# RumiCarGen3-CM5.net
KiCad netlist of a schematic drawn in EAGLE
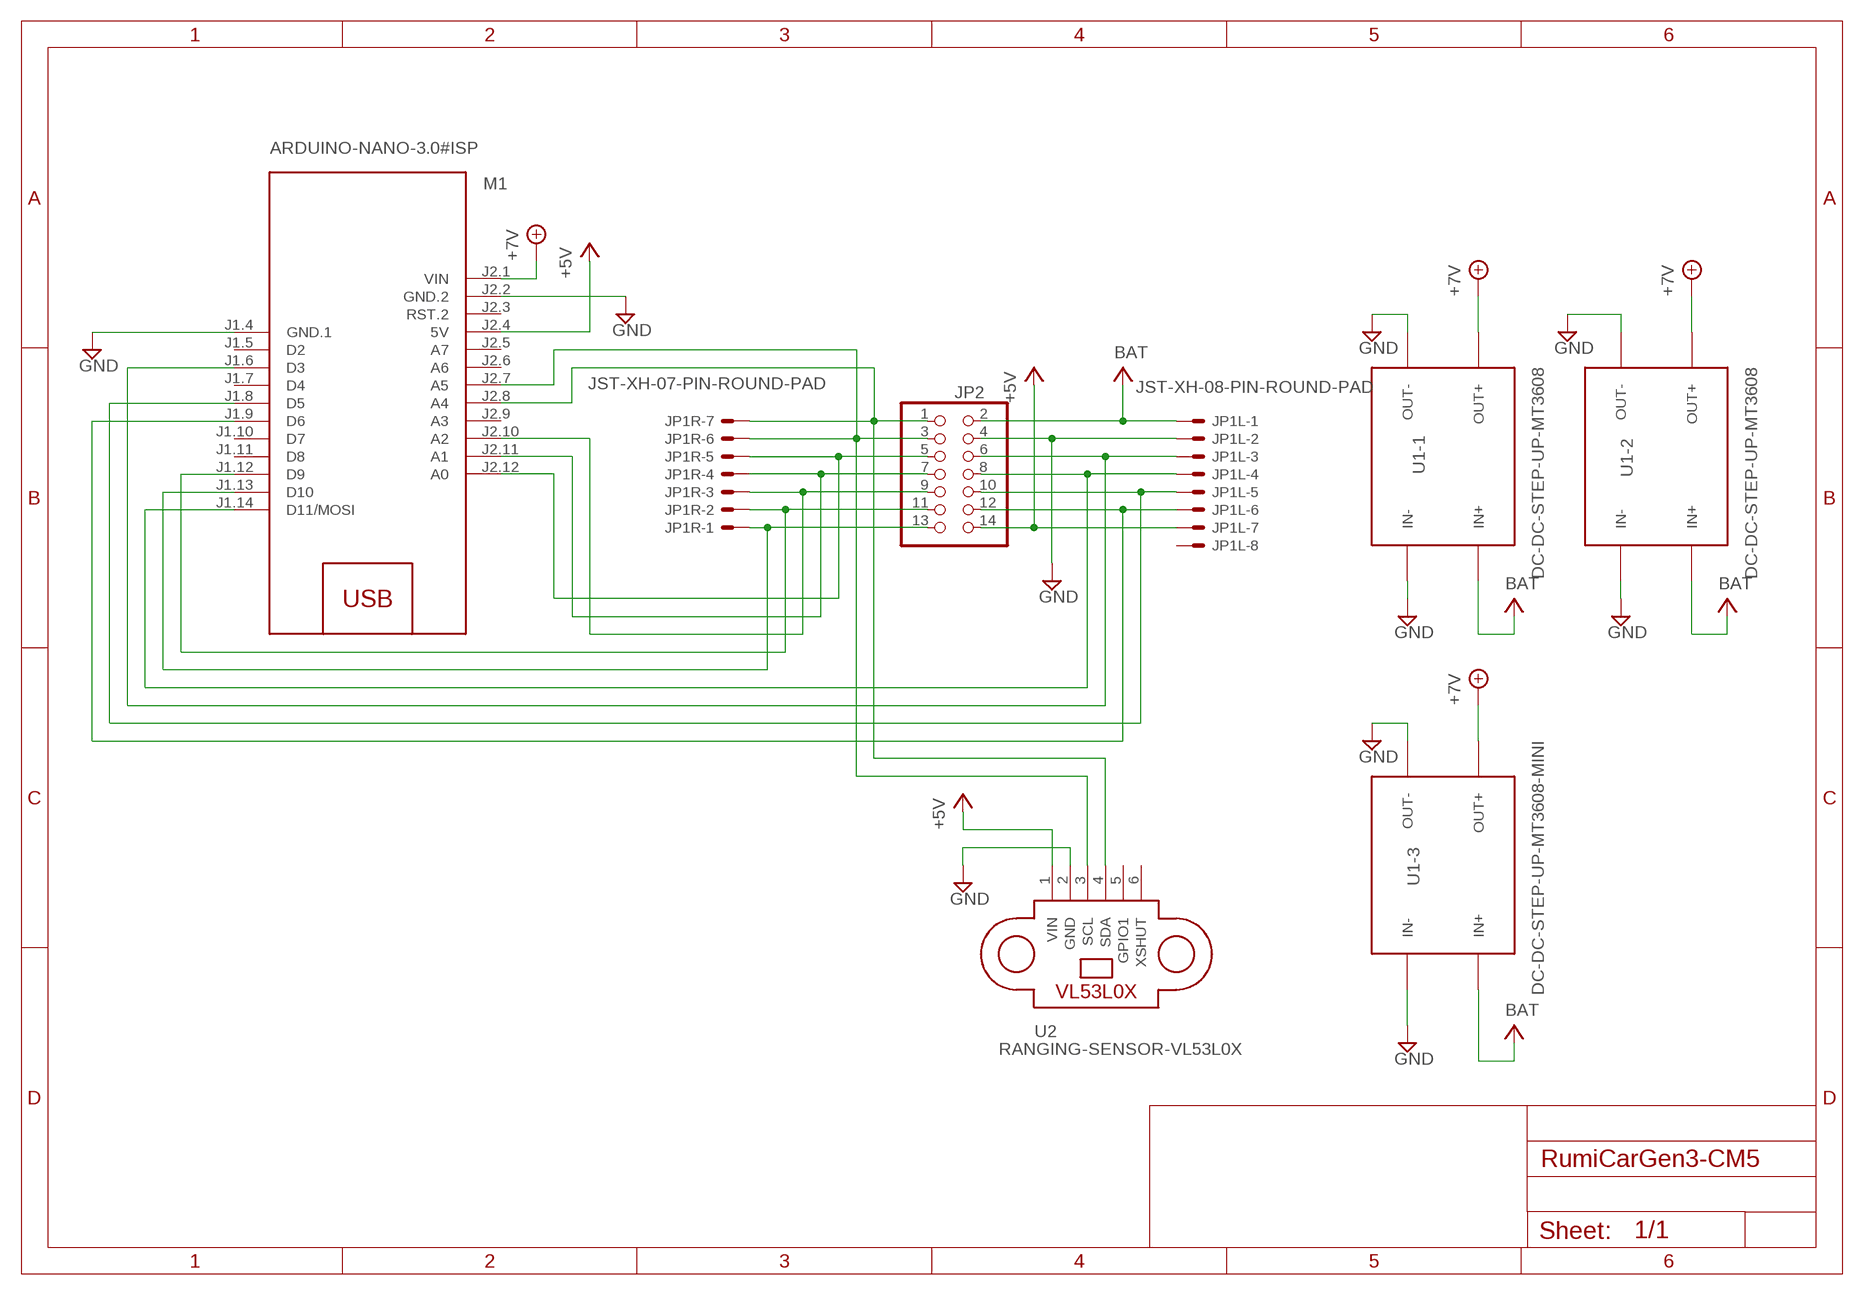
[diagram p0: schematic, sheet 1]

(export (version "E")
  (design (tool "Eeschema 10.0.6"))
  (components
    (comp (ref "JP1L")
      (value "JST-XH-08-PIN-ROUND-PAD")
      (footprint "eagle-import:JST-XH-08-PACKAGE-ROUND-PAD")
      (libsource (lib "eagle-import") (part "JST-XH-08-PIN-ROUND-PAD"))
    )
    (comp (ref "JP1R")
      (value "JST-XH-07-PIN-ROUND-PAD")
      (footprint "eagle-import:JST-XH-07-PACKAGE-ROUND-PAD")
      (libsource (lib "eagle-import") (part "JST-XH-07-PIN-ROUND-PAD"))
    )
    (comp (ref "JP2")
      (value "PINHD-2X7")
      (footprint "eagle-import:2X07")
      (libsource (lib "eagle-import") (part "PINHD-2X7"))
    )
    (comp (ref "M1")
      (value "ARDUINO-NANO-3.0#ISP")
      (footprint "eagle-import:ARDUINO-NANO-3.0#ISP")
      (libsource (lib "eagle-import") (part "ARDUINO-NANO-3.0#ISP"))
    )
    (comp (ref "U1-1")
      (value "DC-DC-STEP-UP-MT3608")
      (footprint "eagle-import:DC-DC-STEP-UP-MT3608")
      (libsource (lib "eagle-import") (part "diy-modules_DC-DC-STEP-UP-MT3608"))
    )
    (comp (ref "U1-2")
      (value "DC-DC-STEP-UP-MT3608")
      (footprint "eagle-import:DC-DC-STEP-UP-MT3608")
      (libsource (lib "eagle-import") (part "DC-DC-STEP-UP-MT3608"))
    )
    (comp (ref "U1-3")
      (value "DC-DC-STEP-UP-MT3608-MINI")
      (footprint "eagle-import:DC-DC-STEP-UP-MT3608-MINI")
      (libsource (lib "eagle-import") (part "DC-DC-STEP-UP-MT3608-MINI"))
    )
    (comp (ref "U2")
      (value "RANGING-SENSOR-VL53L0X")
      (footprint "eagle-import:RANGING-SENSOR-VL53L0X")
      (libsource (lib "eagle-import") (part "RANGING-SENSOR-VL53L0X"))
    )
  )
  (nets
    (net (code "1") (name "+5V") (class "Default")
      (node (ref "JP1L") (pin "7") (pinfunction "S_7") (pintype "passive"))
      (node (ref "JP2") (pin "14") (pinfunction "14_14") (pintype "passive"))
      (node (ref "M1") (pin "J2.4") (pinfunction "5V_J2.4") (pintype "power_in"))
      (node (ref "U2") (pin "1") (pinfunction "VIN_1") (pintype "power_in"))
    )
    (net (code "2") (name "+7V") (class "Default")
      (node (ref "M1") (pin "J2.1") (pinfunction "VIN_J2.1") (pintype "power_in"))
      (node (ref "U1-1") (pin "OUT+") (pinfunction "OUT+_OUT+") (pintype "bidirectional"))
      (node (ref "U1-2") (pin "OUT+") (pinfunction "OUT+_OUT+") (pintype "bidirectional"))
      (node (ref "U1-3") (pin "OUT+") (pinfunction "OUT+_OUT+") (pintype "bidirectional"))
    )
    (net (code "3") (name "BAT") (class "Default")
      (node (ref "JP1L") (pin "1") (pinfunction "S_1") (pintype "passive"))
      (node (ref "JP2") (pin "2") (pinfunction "2_2") (pintype "passive"))
      (node (ref "U1-1") (pin "IN+") (pinfunction "IN+_IN+") (pintype "bidirectional"))
      (node (ref "U1-2") (pin "IN+") (pinfunction "IN+_IN+") (pintype "bidirectional"))
      (node (ref "U1-3") (pin "IN+") (pinfunction "IN+_IN+") (pintype "bidirectional"))
    )
    (net (code "4") (name "GND") (class "Default")
      (node (ref "JP1L") (pin "2") (pinfunction "S_2") (pintype "passive"))
      (node (ref "JP2") (pin "4") (pinfunction "4_4") (pintype "passive"))
      (node (ref "M1") (pin "J1.4") (pinfunction "GND.1_J1.4") (pintype "power_in"))
      (node (ref "M1") (pin "J2.2") (pinfunction "GND.2_J2.2") (pintype "power_in"))
      (node (ref "U1-1") (pin "IN-") (pinfunction "IN-_IN-") (pintype "bidirectional"))
      (node (ref "U1-1") (pin "OUT-") (pinfunction "OUT-_OUT-") (pintype "bidirectional"))
      (node (ref "U1-2") (pin "IN-") (pinfunction "IN-_IN-") (pintype "bidirectional"))
      (node (ref "U1-2") (pin "OUT-") (pinfunction "OUT-_OUT-") (pintype "bidirectional"))
      (node (ref "U1-3") (pin "IN-") (pinfunction "IN-_IN-") (pintype "bidirectional"))
      (node (ref "U1-3") (pin "OUT-") (pinfunction "OUT-_OUT-") (pintype "bidirectional"))
      (node (ref "U2") (pin "2") (pinfunction "GND_2") (pintype "power_in"))
    )
    (net (code "5") (name "Net-(JP1LC-S)") (class "Default")
      (node (ref "JP1L") (pin "3") (pinfunction "S_3") (pintype "passive"))
      (node (ref "JP2") (pin "6") (pinfunction "6_6") (pintype "passive"))
      (node (ref "M1") (pin "J1.6") (pinfunction "D3_J1.6") (pintype "bidirectional"))
    )
    (net (code "6") (name "Net-(JP1LD-S)") (class "Default")
      (node (ref "JP1L") (pin "4") (pinfunction "S_4") (pintype "passive"))
      (node (ref "JP2") (pin "8") (pinfunction "8_8") (pintype "passive"))
      (node (ref "M1") (pin "J1.14") (pinfunction "D11/MOSI_J1.14") (pintype "bidirectional"))
    )
    (net (code "7") (name "Net-(JP1LE-S)") (class "Default")
      (node (ref "JP1L") (pin "5") (pinfunction "S_5") (pintype "passive"))
      (node (ref "JP2") (pin "10") (pinfunction "10_10") (pintype "passive"))
      (node (ref "M1") (pin "J1.8") (pinfunction "D5_J1.8") (pintype "bidirectional"))
    )
    (net (code "8") (name "Net-(JP1LF-S)") (class "Default")
      (node (ref "JP1L") (pin "6") (pinfunction "S_6") (pintype "passive"))
      (node (ref "JP2") (pin "12") (pinfunction "12_12") (pintype "passive"))
      (node (ref "M1") (pin "J1.9") (pinfunction "D6_J1.9") (pintype "bidirectional"))
    )
    (net (code "9") (name "Net-(JP1RA-S)") (class "Default")
      (node (ref "JP1R") (pin "1") (pinfunction "S_1") (pintype "passive"))
      (node (ref "JP2") (pin "13") (pinfunction "13_13") (pintype "passive"))
      (node (ref "M1") (pin "J1.13") (pinfunction "D10_J1.13") (pintype "bidirectional"))
    )
    (net (code "10") (name "Net-(JP1RB-S)") (class "Default")
      (node (ref "JP1R") (pin "2") (pinfunction "S_2") (pintype "passive"))
      (node (ref "JP2") (pin "11") (pinfunction "11_11") (pintype "passive"))
      (node (ref "M1") (pin "J1.12") (pinfunction "D9_J1.12") (pintype "bidirectional"))
    )
    (net (code "11") (name "Net-(JP1RC-S)") (class "Default")
      (node (ref "JP1R") (pin "3") (pinfunction "S_3") (pintype "passive"))
      (node (ref "JP2") (pin "9") (pinfunction "9_9") (pintype "passive"))
      (node (ref "M1") (pin "J2.10") (pinfunction "A2_J2.10") (pintype "bidirectional"))
    )
    (net (code "12") (name "Net-(JP1RD-S)") (class "Default")
      (node (ref "JP1R") (pin "4") (pinfunction "S_4") (pintype "passive"))
      (node (ref "JP2") (pin "7") (pinfunction "7_7") (pintype "passive"))
      (node (ref "M1") (pin "J2.11") (pinfunction "A1_J2.11") (pintype "bidirectional"))
    )
    (net (code "13") (name "Net-(JP1RE-S)") (class "Default")
      (node (ref "JP1R") (pin "5") (pinfunction "S_5") (pintype "passive"))
      (node (ref "JP2") (pin "5") (pinfunction "5_5") (pintype "passive"))
      (node (ref "M1") (pin "J2.12") (pinfunction "A0_J2.12") (pintype "bidirectional"))
    )
    (net (code "14") (name "Net-(JP1RF-S)") (class "Default")
      (node (ref "JP1R") (pin "6") (pinfunction "S_6") (pintype "passive"))
      (node (ref "JP2") (pin "3") (pinfunction "3_3") (pintype "passive"))
      (node (ref "M1") (pin "J2.7") (pinfunction "A5_J2.7") (pintype "bidirectional"))
      (node (ref "U2") (pin "3") (pinfunction "SCL_3") (pintype "bidirectional"))
    )
    (net (code "15") (name "Net-(JP1RG-S)") (class "Default")
      (node (ref "JP1R") (pin "7") (pinfunction "S_7") (pintype "passive"))
      (node (ref "JP2") (pin "1") (pinfunction "1_1") (pintype "passive"))
      (node (ref "M1") (pin "J2.8") (pinfunction "A4_J2.8") (pintype "bidirectional"))
      (node (ref "U2") (pin "4") (pinfunction "SDA_4") (pintype "bidirectional"))
    )
    (net (code "16") (name "unconnected-(JP1LH-S-Pad8)") (class "Default")
      (node (ref "JP1L") (pin "8") (pinfunction "S_8") (pintype "passive"))
    )
    (net (code "17") (name "unconnected-(M1-A3-PadJ2.9)") (class "Default")
      (node (ref "M1") (pin "J2.9") (pinfunction "A3_J2.9") (pintype "bidirectional"))
    )
    (net (code "18") (name "unconnected-(M1-A6-PadJ2.6)") (class "Default")
      (node (ref "M1") (pin "J2.6") (pinfunction "A6_J2.6") (pintype "bidirectional"))
    )
    (net (code "19") (name "unconnected-(M1-A7-PadJ2.5)") (class "Default")
      (node (ref "M1") (pin "J2.5") (pinfunction "A7_J2.5") (pintype "bidirectional"))
    )
    (net (code "20") (name "unconnected-(M1-D2-PadJ1.5)") (class "Default")
      (node (ref "M1") (pin "J1.5") (pinfunction "D2_J1.5") (pintype "bidirectional"))
    )
    (net (code "21") (name "unconnected-(M1-D4-PadJ1.7)") (class "Default")
      (node (ref "M1") (pin "J1.7") (pinfunction "D4_J1.7") (pintype "bidirectional"))
    )
    (net (code "22") (name "unconnected-(M1-D7-PadJ1.10)") (class "Default")
      (node (ref "M1") (pin "J1.10") (pinfunction "D7_J1.10") (pintype "bidirectional"))
    )
    (net (code "23") (name "unconnected-(M1-D8-PadJ1.11)") (class "Default")
      (node (ref "M1") (pin "J1.11") (pinfunction "D8_J1.11") (pintype "bidirectional"))
    )
    (net (code "24") (name "unconnected-(M1-RST.2-PadJ2.3)") (class "Default")
      (node (ref "M1") (pin "J2.3") (pinfunction "RST.2_J2.3") (pintype "bidirectional"))
    )
    (net (code "25") (name "unconnected-(U2-GPIO1-Pad5)") (class "Default")
      (node (ref "U2") (pin "5") (pinfunction "GPIO1_5") (pintype "bidirectional"))
    )
    (net (code "26") (name "unconnected-(U2-XSHUT-Pad6)") (class "Default")
      (node (ref "U2") (pin "6") (pinfunction "XSHUT_6") (pintype "bidirectional"))
    )
  )
)
